# ESP_CO2_V0_30.net
KiCad netlist of a schematic drawn in EAGLE
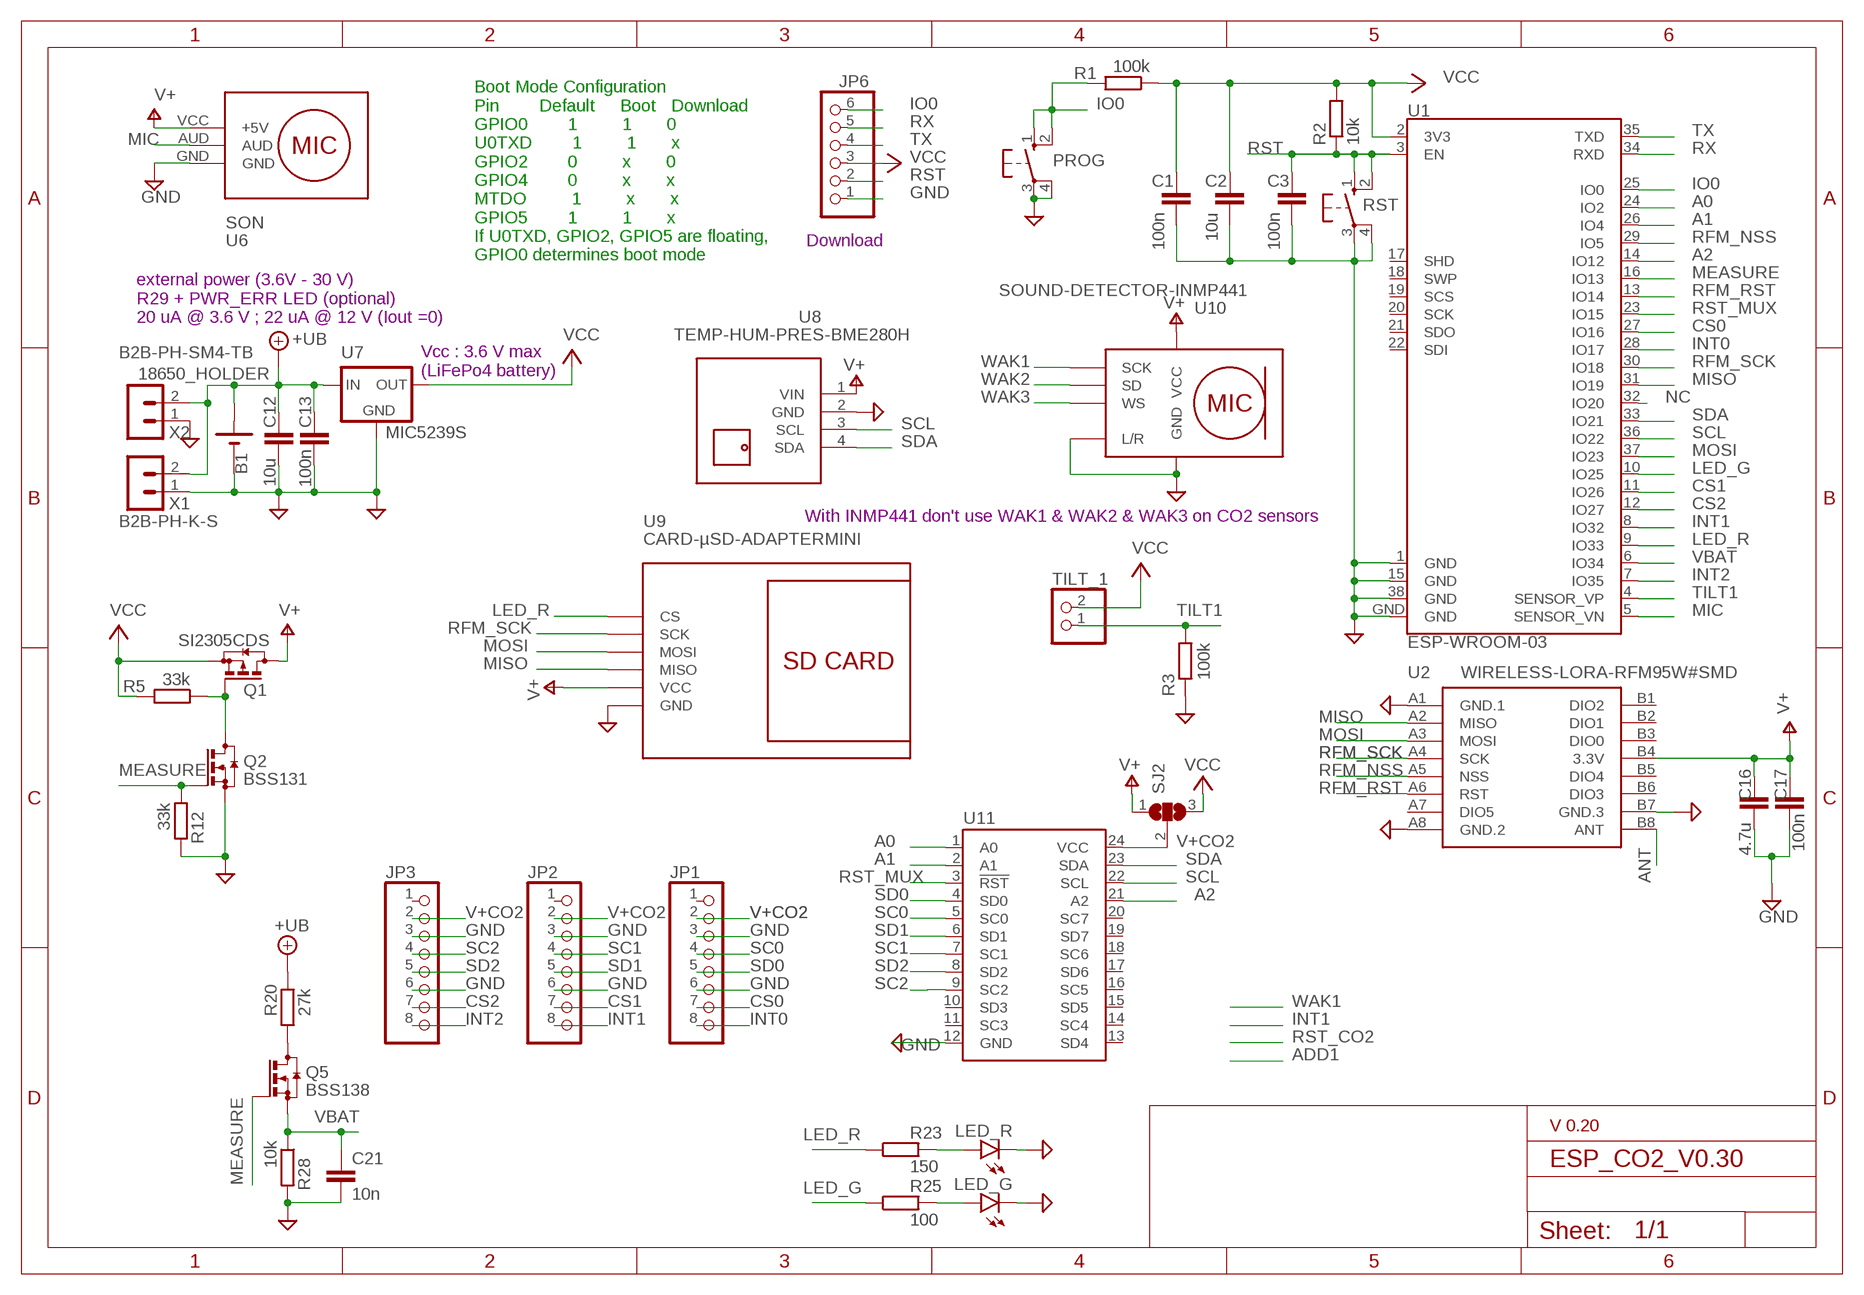
[diagram p0: schematic, sheet 1]

(export (version "E")
  (design (tool "Eeschema 10.0.6"))
  (components
    (comp (ref "B1")
      (value "18650_HOLDER")
      (footprint "eagle-import:18650")
      (libsource (lib "eagle-import") (part "18650_HOLDER"))
    )
    (comp (ref "C1")
      (value "100n")
      (footprint "eagle-import:C1206")
      (libsource (lib "eagle-import") (part "CC1206"))
    )
    (comp (ref "C2")
      (value "10u")
      (footprint "eagle-import:C1206")
      (libsource (lib "eagle-import") (part "CC1206"))
    )
    (comp (ref "C3")
      (value "100n")
      (footprint "eagle-import:C1206")
      (libsource (lib "eagle-import") (part "CC1206"))
    )
    (comp (ref "C12")
      (value "10u")
      (footprint "eagle-import:C1206")
      (libsource (lib "eagle-import") (part "CC1206"))
    )
    (comp (ref "C13")
      (value "100n")
      (footprint "eagle-import:C1206")
      (libsource (lib "eagle-import") (part "CC1206"))
    )
    (comp (ref "C16")
      (value "4.7u")
      (footprint "eagle-import:C1206")
      (libsource (lib "eagle-import") (part "CC1206"))
    )
    (comp (ref "C17")
      (value "100n")
      (footprint "eagle-import:C1206")
      (libsource (lib "eagle-import") (part "CC1206"))
    )
    (comp (ref "C21")
      (value "10n")
      (footprint "eagle-import:C1206")
      (libsource (lib "eagle-import") (part "CC1206"))
    )
    (comp (ref "JP1")
      (value "PINHD-1X8")
      (footprint "eagle-import:1X08")
      (libsource (lib "eagle-import") (part "PINHD-1X8"))
    )
    (comp (ref "JP2")
      (value "PINHD-1X8")
      (footprint "eagle-import:1X08")
      (libsource (lib "eagle-import") (part "PINHD-1X8"))
    )
    (comp (ref "JP3")
      (value "PINHD-1X8")
      (footprint "eagle-import:1X08")
      (libsource (lib "eagle-import") (part "PINHD-1X8"))
    )
    (comp (ref "JP6")
      (value "PINHD-1X6/90")
      (footprint "eagle-import:1X06_90")
      (libsource (lib "eagle-import") (part "PINHD-1X6/90"))
    )
    (comp (ref "LED_G")
      (value "LEDSML0805")
      (footprint "eagle-import:SML0805")
      (libsource (lib "eagle-import") (part "LEDSML0805"))
    )
    (comp (ref "LED_R")
      (value "LEDSML0805")
      (footprint "eagle-import:SML0805")
      (libsource (lib "eagle-import") (part "LEDSML0805"))
    )
    (comp (ref "PROG")
      (value "10-XX")
      (footprint "eagle-import:B3F-10XX")
      (fields (field (name "MPN") "B3F-1000"))
      (libsource (lib "eagle-import") (part "10-XX"))
    )
    (comp (ref "Q1")
      (value "SI2305CDS")
      (footprint "eagle-import:SOT23")
      (libsource (lib "eagle-import") (part "SI2305CDS"))
    )
    (comp (ref "Q2")
      (value "BSS131")
      (footprint "eagle-import:SOT23")
      (libsource (lib "eagle-import") (part "BSS131"))
    )
    (comp (ref "Q5")
      (value "BSS138")
      (footprint "eagle-import:SOT23")
      (libsource (lib "eagle-import") (part "BSS138"))
    )
    (comp (ref "R1")
      (value "100k")
      (footprint "eagle-import:R1206")
      (libsource (lib "eagle-import") (part "RR1206"))
    )
    (comp (ref "R2")
      (value "10k")
      (footprint "eagle-import:R1206")
      (libsource (lib "eagle-import") (part "RR1206"))
    )
    (comp (ref "R3")
      (value "100k")
      (footprint "eagle-import:R1206")
      (libsource (lib "eagle-import") (part "RR1206"))
    )
    (comp (ref "R5")
      (value "33k")
      (footprint "eagle-import:R1206")
      (libsource (lib "eagle-import") (part "RR1206"))
    )
    (comp (ref "R12")
      (value "33k")
      (footprint "eagle-import:R1206")
      (libsource (lib "eagle-import") (part "RR1206"))
    )
    (comp (ref "R20")
      (value "27k")
      (footprint "eagle-import:R1206")
      (libsource (lib "eagle-import") (part "RR1206"))
    )
    (comp (ref "R23")
      (value "150")
      (footprint "eagle-import:R1206")
      (libsource (lib "eagle-import") (part "RR1206"))
    )
    (comp (ref "R25")
      (value "100")
      (footprint "eagle-import:R1206")
      (libsource (lib "eagle-import") (part "RR1206"))
    )
    (comp (ref "R28")
      (value "10k")
      (footprint "eagle-import:R1206")
      (libsource (lib "eagle-import") (part "RR1206"))
    )
    (comp (ref "RST")
      (value "10-XX")
      (footprint "eagle-import:B3F-10XX")
      (fields (field (name "MPN") "B3F-1000"))
      (libsource (lib "eagle-import") (part "10-XX"))
    )
    (comp (ref "SJ2")
      (value "SJ2W")
      (footprint "eagle-import:SJ_2")
      (libsource (lib "eagle-import") (part "SJ2W"))
    )
    (comp (ref "TILT_1")
      (value "PINHD-1X2")
      (footprint "eagle-import:1X02")
      (libsource (lib "eagle-import") (part "PINHD-1X2"))
    )
    (comp (ref "U1")
      (value "ESP-WROOM-03")
      (footprint "eagle-import:ESP-WROOM-03")
      (libsource (lib "eagle-import") (part "ESP-WROOM-03"))
    )
    (comp (ref "U2")
      (value "WIRELESS-LORA-RFM95W#SMD")
      (footprint "eagle-import:WIRELESS-LORA-RFM95W#SMD")
      (libsource (lib "eagle-import") (part "WIRELESS-LORA-RFM95W#SMD"))
    )
    (comp (ref "U6")
      (value "SON")
      (footprint "eagle-import:SON")
      (libsource (lib "eagle-import") (part "SON"))
    )
    (comp (ref "U7")
      (value "MIC5239S")
      (footprint "eagle-import:SOT223")
      (libsource (lib "eagle-import") (part "MIC5239S"))
    )
    (comp (ref "U8")
      (value "TEMP-HUM-PRES-BME280H")
      (footprint "eagle-import:TEMP-HUM-PRES-BME280-H")
      (libsource (lib "eagle-import") (part "TEMP-HUM-PRES-BME280H"))
    )
    (comp (ref "U9")
      (value "CARD-µSD-ADAPTERMINI")
      (footprint "eagle-import:CARD-MINI--µSD-READER")
      (libsource (lib "eagle-import") (part "CARD-µSD-ADAPTERMINI"))
    )
    (comp (ref "U10")
      (value "SOUND-DETECTOR-INMP441")
      (footprint "eagle-import:SOUND-DETECTOR-INMP441")
      (libsource (lib "eagle-import") (part "SOUND-DETECTOR-INMP441"))
    )
    (comp (ref "U11")
      (value "PCA9548A")
      (footprint "eagle-import:TSSOP28")
      (libsource (lib "eagle-import") (part "PCA9548A"))
    )
    (comp (ref "X1")
      (value "B2B-PH-K-S")
      (footprint "eagle-import:B2B-PH-K-S")
      (libsource (lib "eagle-import") (part "B2B-PH-K-S"))
    )
    (comp (ref "X2")
      (value "B2B-PH-SM4-TB")
      (footprint "eagle-import:B2B-PH-SM4-TB")
      (libsource (lib "eagle-import") (part "B2B-PH-SM4-TB"))
    )
  )
  (nets
    (net (code "1") (name "+UB") (class "Default")
      (node (ref "B1") (pin "+") (pinfunction "+_+") (pintype "passive"))
      (node (ref "C12") (pin "1") (pinfunction "1_1") (pintype "passive"))
      (node (ref "C13") (pin "1") (pinfunction "1_1") (pintype "passive"))
      (node (ref "R20") (pin "2") (pinfunction "2_2") (pintype "passive"))
      (node (ref "U7") (pin "1") (pinfunction "IN_1") (pintype "input"))
      (node (ref "X1") (pin "2") (pinfunction "2_2") (pintype "passive"))
      (node (ref "X2") (pin "2") (pinfunction "2_2") (pintype "passive"))
    )
    (net (code "2") (name "/A0") (class "Default")
      (node (ref "U1") (pin "24") (pinfunction "IO2_24") (pintype "bidirectional"))
      (node (ref "U11") (pin "1") (pinfunction "A0_1") (pintype "bidirectional"))
    )
    (net (code "3") (name "/A1") (class "Default")
      (node (ref "U1") (pin "26") (pinfunction "IO4_26") (pintype "bidirectional"))
      (node (ref "U11") (pin "2") (pinfunction "A1_2") (pintype "bidirectional"))
    )
    (net (code "4") (name "/A2") (class "Default")
      (node (ref "U1") (pin "14") (pinfunction "IO12_14") (pintype "bidirectional"))
      (node (ref "U11") (pin "21") (pinfunction "A2_21") (pintype "bidirectional"))
    )
    (net (code "6") (name "/ANT") (class "Default")
      (node (ref "U2") (pin "B8") (pinfunction "ANT_B8") (pintype "passive"))
    )
    (net (code "7") (name "/CS0") (class "Default")
      (node (ref "JP1") (pin "7") (pinfunction "7_7") (pintype "passive"))
      (node (ref "U1") (pin "27") (pinfunction "IO16_27") (pintype "bidirectional"))
    )
    (net (code "8") (name "/CS1") (class "Default")
      (node (ref "JP2") (pin "7") (pinfunction "7_7") (pintype "passive"))
      (node (ref "U1") (pin "11") (pinfunction "IO26_11") (pintype "bidirectional"))
    )
    (net (code "9") (name "/CS2") (class "Default")
      (node (ref "JP3") (pin "7") (pinfunction "7_7") (pintype "passive"))
      (node (ref "U1") (pin "12") (pinfunction "IO27_12") (pintype "bidirectional"))
    )
    (net (code "10") (name "/INT0") (class "Default")
      (node (ref "JP1") (pin "8") (pinfunction "8_8") (pintype "passive"))
      (node (ref "U1") (pin "28") (pinfunction "IO17_28") (pintype "bidirectional"))
    )
    (net (code "11") (name "/INT1") (class "Default")
      (node (ref "JP2") (pin "8") (pinfunction "8_8") (pintype "passive"))
      (node (ref "U1") (pin "8") (pinfunction "IO32_8") (pintype "bidirectional"))
    )
    (net (code "12") (name "/INT2") (class "Default")
      (node (ref "JP3") (pin "8") (pinfunction "8_8") (pintype "passive"))
      (node (ref "U1") (pin "7") (pinfunction "IO35_7") (pintype "bidirectional"))
    )
    (net (code "13") (name "/IO0") (class "Default")
      (node (ref "JP6") (pin "6") (pinfunction "6_6") (pintype "passive"))
      (node (ref "PROG") (pin "1") (pinfunction "S_1") (pintype "passive"))
      (node (ref "PROG") (pin "2") (pinfunction "S1_2") (pintype "passive"))
      (node (ref "R1") (pin "2") (pinfunction "2_2") (pintype "passive"))
      (node (ref "U1") (pin "25") (pinfunction "IO0_25") (pintype "bidirectional"))
    )
    (net (code "14") (name "/LED_G") (class "Default")
      (node (ref "R25") (pin "1") (pinfunction "1_1") (pintype "passive"))
      (node (ref "U1") (pin "10") (pinfunction "IO25_10") (pintype "bidirectional"))
    )
    (net (code "15") (name "/LED_R") (class "Default")
      (node (ref "R23") (pin "1") (pinfunction "1_1") (pintype "passive"))
      (node (ref "U1") (pin "9") (pinfunction "IO33_9") (pintype "bidirectional"))
      (node (ref "U9") (pin "CS") (pinfunction "CS_CS") (pintype "bidirectional"))
    )
    (net (code "16") (name "/MEASURE") (class "Default")
      (node (ref "Q2") (pin "1") (pinfunction "G_1") (pintype "passive"))
      (node (ref "Q5") (pin "1") (pinfunction "G_1") (pintype "passive"))
      (node (ref "R12") (pin "1") (pinfunction "1_1") (pintype "passive"))
      (node (ref "U1") (pin "16") (pinfunction "IO13_16") (pintype "bidirectional"))
    )
    (net (code "17") (name "/MIC") (class "Default")
      (node (ref "U1") (pin "5") (pinfunction "SENSOR_VN_5") (pintype "bidirectional"))
      (node (ref "U6") (pin "AUD") (pinfunction "AUD_AUD") (pintype "output"))
    )
    (net (code "18") (name "/MISO") (class "Default")
      (node (ref "U1") (pin "31") (pinfunction "IO19_31") (pintype "bidirectional"))
      (node (ref "U2") (pin "A2") (pinfunction "MISO_A2") (pintype "bidirectional"))
      (node (ref "U9") (pin "MISO") (pinfunction "MISO_MISO") (pintype "bidirectional"))
    )
    (net (code "19") (name "/MOSI") (class "Default")
      (node (ref "U1") (pin "37") (pinfunction "IO23_37") (pintype "bidirectional"))
      (node (ref "U2") (pin "A3") (pinfunction "MOSI_A3") (pintype "bidirectional"))
      (node (ref "U9") (pin "MOSI") (pinfunction "MOSI_MOSI") (pintype "bidirectional"))
    )
    (net (code "20") (name "/NC") (class "Default")
      (node (ref "U1") (pin "32") (pinfunction "IO20_32") (pintype "bidirectional"))
    )
    (net (code "21") (name "/RFM_NSS") (class "Default")
      (node (ref "U1") (pin "29") (pinfunction "IO5_29") (pintype "bidirectional"))
      (node (ref "U2") (pin "A5") (pinfunction "NSS_A5") (pintype "bidirectional"))
    )
    (net (code "22") (name "/RFM_RST") (class "Default")
      (node (ref "U1") (pin "13") (pinfunction "IO14_13") (pintype "bidirectional"))
      (node (ref "U2") (pin "A6") (pinfunction "RST_A6") (pintype "bidirectional"))
    )
    (net (code "23") (name "/RFM_SCK") (class "Default")
      (node (ref "U1") (pin "30") (pinfunction "IO18_30") (pintype "bidirectional"))
      (node (ref "U2") (pin "A4") (pinfunction "SCK_A4") (pintype "bidirectional"))
      (node (ref "U9") (pin "SCK") (pinfunction "SCK_SCK") (pintype "bidirectional"))
    )
    (net (code "24") (name "/RST") (class "Default")
      (node (ref "C3") (pin "1") (pinfunction "1_1") (pintype "passive"))
      (node (ref "JP6") (pin "2") (pinfunction "2_2") (pintype "passive"))
      (node (ref "R2") (pin "1") (pinfunction "1_1") (pintype "passive"))
      (node (ref "RST") (pin "1") (pinfunction "S_1") (pintype "passive"))
      (node (ref "RST") (pin "2") (pinfunction "S1_2") (pintype "passive"))
      (node (ref "U1") (pin "3") (pinfunction "EN_3") (pintype "bidirectional"))
    )
    (net (code "26") (name "/RST_MUX") (class "Default")
      (node (ref "U1") (pin "23") (pinfunction "IO15_23") (pintype "bidirectional"))
      (node (ref "U11") (pin "3") (pinfunction "~{RST}_3") (pintype "bidirectional"))
    )
    (net (code "27") (name "/RX") (class "Default")
      (node (ref "JP6") (pin "5") (pinfunction "5_5") (pintype "passive"))
      (node (ref "U1") (pin "34") (pinfunction "RXD_34") (pintype "bidirectional"))
    )
    (net (code "28") (name "/SC0") (class "Default")
      (node (ref "JP1") (pin "4") (pinfunction "4_4") (pintype "passive"))
      (node (ref "U11") (pin "5") (pinfunction "SC0_5") (pintype "bidirectional"))
    )
    (net (code "29") (name "/SC1") (class "Default")
      (node (ref "JP2") (pin "4") (pinfunction "4_4") (pintype "passive"))
      (node (ref "U11") (pin "7") (pinfunction "SC1_7") (pintype "bidirectional"))
    )
    (net (code "30") (name "/SC2") (class "Default")
      (node (ref "JP3") (pin "4") (pinfunction "4_4") (pintype "passive"))
      (node (ref "U11") (pin "9") (pinfunction "SC2_9") (pintype "bidirectional"))
    )
    (net (code "31") (name "/SCL") (class "Default")
      (node (ref "U1") (pin "36") (pinfunction "IO22_36") (pintype "bidirectional"))
      (node (ref "U11") (pin "22") (pinfunction "SCL_22") (pintype "bidirectional"))
      (node (ref "U8") (pin "3") (pinfunction "SCL_3") (pintype "bidirectional"))
    )
    (net (code "32") (name "/SD0") (class "Default")
      (node (ref "JP1") (pin "5") (pinfunction "5_5") (pintype "passive"))
      (node (ref "U11") (pin "4") (pinfunction "SD0_4") (pintype "bidirectional"))
    )
    (net (code "33") (name "/SD1") (class "Default")
      (node (ref "JP2") (pin "5") (pinfunction "5_5") (pintype "passive"))
      (node (ref "U11") (pin "6") (pinfunction "SD1_6") (pintype "bidirectional"))
    )
    (net (code "34") (name "/SD2") (class "Default")
      (node (ref "JP3") (pin "5") (pinfunction "5_5") (pintype "passive"))
      (node (ref "U11") (pin "8") (pinfunction "SD2_8") (pintype "bidirectional"))
    )
    (net (code "35") (name "/SDA") (class "Default")
      (node (ref "U1") (pin "33") (pinfunction "IO21_33") (pintype "bidirectional"))
      (node (ref "U11") (pin "23") (pinfunction "SDA_23") (pintype "bidirectional"))
      (node (ref "U8") (pin "4") (pinfunction "SDA_4") (pintype "bidirectional"))
    )
    (net (code "36") (name "/TILT1") (class "Default")
      (node (ref "R3") (pin "1") (pinfunction "1_1") (pintype "passive"))
      (node (ref "TILT_1") (pin "1") (pinfunction "1_1") (pintype "passive"))
      (node (ref "U1") (pin "4") (pinfunction "SENSOR_VP_4") (pintype "bidirectional"))
    )
    (net (code "37") (name "/TX") (class "Default")
      (node (ref "JP6") (pin "4") (pinfunction "4_4") (pintype "passive"))
      (node (ref "U1") (pin "35") (pinfunction "TXD_35") (pintype "bidirectional"))
    )
    (net (code "38") (name "/V+CO2") (class "Default")
      (node (ref "JP1") (pin "2") (pinfunction "2_2") (pintype "passive"))
      (node (ref "JP2") (pin "2") (pinfunction "2_2") (pintype "passive"))
      (node (ref "JP3") (pin "2") (pinfunction "2_2") (pintype "passive"))
      (node (ref "SJ2") (pin "2") (pinfunction "2_2") (pintype "passive"))
      (node (ref "U11") (pin "24") (pinfunction "VCC_24") (pintype "bidirectional"))
    )
    (net (code "39") (name "/VBAT") (class "Default")
      (node (ref "C21") (pin "1") (pinfunction "1_1") (pintype "passive"))
      (node (ref "Q5") (pin "2") (pinfunction "S_2") (pintype "passive"))
      (node (ref "R28") (pin "1") (pinfunction "1_1") (pintype "passive"))
      (node (ref "U1") (pin "6") (pinfunction "IO34_6") (pintype "bidirectional"))
    )
    (net (code "40") (name "/WAK1") (class "Default")
      (node (ref "U10") (pin "SCK") (pinfunction "SCK_SCK") (pintype "output"))
    )
    (net (code "41") (name "/WAK2") (class "Default")
      (node (ref "U10") (pin "SD") (pinfunction "SD_SD") (pintype "output"))
    )
    (net (code "42") (name "/WAK3") (class "Default")
      (node (ref "U10") (pin "WS") (pinfunction "WS_WS") (pintype "output"))
    )
    (net (code "43") (name "GND") (class "Default")
      (node (ref "B1") (pin "-") (pinfunction "-_-") (pintype "passive"))
      (node (ref "C1") (pin "2") (pinfunction "2_2") (pintype "passive"))
      (node (ref "C12") (pin "2") (pinfunction "2_2") (pintype "passive"))
      (node (ref "C13") (pin "2") (pinfunction "2_2") (pintype "passive"))
      (node (ref "C16") (pin "2") (pinfunction "2_2") (pintype "passive"))
      (node (ref "C17") (pin "2") (pinfunction "2_2") (pintype "passive"))
      (node (ref "C2") (pin "2") (pinfunction "2_2") (pintype "passive"))
      (node (ref "C21") (pin "2") (pinfunction "2_2") (pintype "passive"))
      (node (ref "C3") (pin "2") (pinfunction "2_2") (pintype "passive"))
      (node (ref "JP1") (pin "3") (pinfunction "3_3") (pintype "passive"))
      (node (ref "JP1") (pin "6") (pinfunction "6_6") (pintype "passive"))
      (node (ref "JP2") (pin "3") (pinfunction "3_3") (pintype "passive"))
      (node (ref "JP2") (pin "6") (pinfunction "6_6") (pintype "passive"))
      (node (ref "JP3") (pin "3") (pinfunction "3_3") (pintype "passive"))
      (node (ref "JP3") (pin "6") (pinfunction "6_6") (pintype "passive"))
      (node (ref "JP6") (pin "1") (pinfunction "1_1") (pintype "passive"))
      (node (ref "LED_G") (pin "C") (pinfunction "C_C") (pintype "passive"))
      (node (ref "LED_R") (pin "C") (pinfunction "C_C") (pintype "passive"))
      (node (ref "PROG") (pin "3") (pinfunction "P_3") (pintype "passive"))
      (node (ref "PROG") (pin "4") (pinfunction "P1_4") (pintype "passive"))
      (node (ref "Q2") (pin "2") (pinfunction "S_2") (pintype "passive"))
      (node (ref "R12") (pin "2") (pinfunction "2_2") (pintype "passive"))
      (node (ref "R28") (pin "2") (pinfunction "2_2") (pintype "passive"))
      (node (ref "R3") (pin "2") (pinfunction "2_2") (pintype "passive"))
      (node (ref "RST") (pin "3") (pinfunction "P_3") (pintype "passive"))
      (node (ref "RST") (pin "4") (pinfunction "P1_4") (pintype "passive"))
      (node (ref "U1") (pin "1") (pinfunction "GND_1") (pintype "bidirectional"))
      (node (ref "U1") (pin "15") (pinfunction "GND_15") (pintype "bidirectional"))
      (node (ref "U1") (pin "38") (pinfunction "GND_38") (pintype "bidirectional"))
      (node (ref "U1") (pin "GND") (pinfunction "GND_GND") (pintype "bidirectional"))
      (node (ref "U10") (pin "GND") (pinfunction "GND_GND") (pintype "power_in"))
      (node (ref "U10") (pin "L/R") (pinfunction "L/R_L/R") (pintype "output"))
      (node (ref "U11") (pin "12") (pinfunction "GND_12") (pintype "bidirectional"))
      (node (ref "U2") (pin "A1") (pinfunction "GND.1_A1") (pintype "power_in"))
      (node (ref "U2") (pin "A8") (pinfunction "GND.2_A8") (pintype "power_in"))
      (node (ref "U2") (pin "B7") (pinfunction "GND.3_B7") (pintype "power_in"))
      (node (ref "U6") (pin "GND") (pinfunction "GND_GND") (pintype "power_in"))
      (node (ref "U7") (pin "2") (pinfunction "GND_2") (pintype "passive"))
      (node (ref "U7") (pin "4") (pinfunction "GND_4") (pintype "passive"))
      (node (ref "U8") (pin "2") (pinfunction "GND_2") (pintype "power_in"))
      (node (ref "U9") (pin "GND") (pinfunction "GND_GND") (pintype "power_in"))
      (node (ref "X1") (pin "1") (pinfunction "1_1") (pintype "passive"))
      (node (ref "X2") (pin "1") (pinfunction "1_1") (pintype "passive"))
    )
    (net (code "44") (name "Net-(LED_G-PadA)") (class "Default")
      (node (ref "LED_G") (pin "A") (pinfunction "A_A") (pintype "passive"))
      (node (ref "R25") (pin "2") (pinfunction "2_2") (pintype "passive"))
    )
    (net (code "45") (name "Net-(LED_R-PadA)") (class "Default")
      (node (ref "LED_R") (pin "A") (pinfunction "A_A") (pintype "passive"))
      (node (ref "R23") (pin "2") (pinfunction "2_2") (pintype "passive"))
    )
    (net (code "46") (name "Net-(Q1-G)") (class "Default")
      (node (ref "Q1") (pin "1") (pinfunction "G_1") (pintype "passive"))
      (node (ref "Q2") (pin "3") (pinfunction "D_3") (pintype "passive"))
      (node (ref "R5") (pin "1") (pinfunction "1_1") (pintype "passive"))
    )
    (net (code "47") (name "Net-(Q5-D)") (class "Default")
      (node (ref "Q5") (pin "3") (pinfunction "D_3") (pintype "passive"))
      (node (ref "R20") (pin "1") (pinfunction "1_1") (pintype "passive"))
    )
    (net (code "48") (name "V+") (class "Default")
      (node (ref "C16") (pin "1") (pinfunction "1_1") (pintype "passive"))
      (node (ref "C17") (pin "1") (pinfunction "1_1") (pintype "passive"))
      (node (ref "Q1") (pin "3") (pinfunction "D_3") (pintype "passive"))
      (node (ref "SJ2") (pin "1") (pinfunction "1_1") (pintype "passive"))
      (node (ref "U10") (pin "VDD") (pinfunction "VCC_VDD") (pintype "power_in"))
      (node (ref "U2") (pin "B4") (pinfunction "3.3V_B4") (pintype "power_in"))
      (node (ref "U6") (pin "VCC") (pinfunction "+5V_VCC") (pintype "power_in"))
      (node (ref "U8") (pin "1") (pinfunction "VIN_1") (pintype "power_in"))
      (node (ref "U9") (pin "VCC") (pinfunction "VCC_VCC") (pintype "power_in"))
    )
    (net (code "49") (name "VCC") (class "Default")
      (node (ref "C1") (pin "1") (pinfunction "1_1") (pintype "passive"))
      (node (ref "C2") (pin "1") (pinfunction "1_1") (pintype "passive"))
      (node (ref "JP6") (pin "3") (pinfunction "3_3") (pintype "passive"))
      (node (ref "Q1") (pin "2") (pinfunction "S_2") (pintype "passive"))
      (node (ref "R1") (pin "1") (pinfunction "1_1") (pintype "passive"))
      (node (ref "R2") (pin "2") (pinfunction "2_2") (pintype "passive"))
      (node (ref "R5") (pin "2") (pinfunction "2_2") (pintype "passive"))
      (node (ref "SJ2") (pin "3") (pinfunction "3_3") (pintype "passive"))
      (node (ref "TILT_1") (pin "2") (pinfunction "2_2") (pintype "passive"))
      (node (ref "U1") (pin "2") (pinfunction "3V3_2") (pintype "bidirectional"))
      (node (ref "U7") (pin "3") (pinfunction "OUT_3") (pintype "passive"))
    )
    (net (code "50") (name "unconnected-(JP1-Pad1)") (class "Default")
      (node (ref "JP1") (pin "1") (pinfunction "1_1") (pintype "passive"))
    )
    (net (code "51") (name "unconnected-(JP2-Pad1)") (class "Default")
      (node (ref "JP2") (pin "1") (pinfunction "1_1") (pintype "passive"))
    )
    (net (code "52") (name "unconnected-(JP3-Pad1)") (class "Default")
      (node (ref "JP3") (pin "1") (pinfunction "1_1") (pintype "passive"))
    )
    (net (code "53") (name "unconnected-(U1-SCK-Pad20)") (class "Default")
      (node (ref "U1") (pin "20") (pinfunction "SCK_20") (pintype "bidirectional"))
    )
    (net (code "54") (name "unconnected-(U1-SCS-Pad19)") (class "Default")
      (node (ref "U1") (pin "19") (pinfunction "SCS_19") (pintype "bidirectional"))
    )
    (net (code "55") (name "unconnected-(U1-SDI-Pad22)") (class "Default")
      (node (ref "U1") (pin "22") (pinfunction "SDI_22") (pintype "bidirectional"))
    )
    (net (code "56") (name "unconnected-(U1-SDO-Pad21)") (class "Default")
      (node (ref "U1") (pin "21") (pinfunction "SDO_21") (pintype "bidirectional"))
    )
    (net (code "57") (name "unconnected-(U1-SHD-Pad17)") (class "Default")
      (node (ref "U1") (pin "17") (pinfunction "SHD_17") (pintype "bidirectional"))
    )
    (net (code "58") (name "unconnected-(U1-SWP-Pad18)") (class "Default")
      (node (ref "U1") (pin "18") (pinfunction "SWP_18") (pintype "bidirectional"))
    )
    (net (code "59") (name "unconnected-(U2-DIO0-PadB3)") (class "Default")
      (node (ref "U2") (pin "B3") (pinfunction "DIO0_B3") (pintype "bidirectional"))
    )
    (net (code "60") (name "unconnected-(U2-DIO1-PadB2)") (class "Default")
      (node (ref "U2") (pin "B2") (pinfunction "DIO1_B2") (pintype "bidirectional"))
    )
    (net (code "61") (name "unconnected-(U2-DIO2-PadB1)") (class "Default")
      (node (ref "U2") (pin "B1") (pinfunction "DIO2_B1") (pintype "bidirectional"))
    )
    (net (code "62") (name "unconnected-(U2-DIO3-PadB6)") (class "Default")
      (node (ref "U2") (pin "B6") (pinfunction "DIO3_B6") (pintype "bidirectional"))
    )
    (net (code "63") (name "unconnected-(U2-DIO4-PadB5)") (class "Default")
      (node (ref "U2") (pin "B5") (pinfunction "DIO4_B5") (pintype "bidirectional"))
    )
    (net (code "64") (name "unconnected-(U2-DIO5-PadA7)") (class "Default")
      (node (ref "U2") (pin "A7") (pinfunction "DIO5_A7") (pintype "bidirectional"))
    )
    (net (code "65") (name "unconnected-(U11-SC3-Pad11)") (class "Default")
      (node (ref "U11") (pin "11") (pinfunction "SC3_11") (pintype "bidirectional"))
    )
    (net (code "66") (name "unconnected-(U11-SC4-Pad14)") (class "Default")
      (node (ref "U11") (pin "14") (pinfunction "SC4_14") (pintype "bidirectional"))
    )
    (net (code "67") (name "unconnected-(U11-SC5-Pad16)") (class "Default")
      (node (ref "U11") (pin "16") (pinfunction "SC5_16") (pintype "bidirectional"))
    )
    (net (code "68") (name "unconnected-(U11-SC6-Pad18)") (class "Default")
      (node (ref "U11") (pin "18") (pinfunction "SC6_18") (pintype "bidirectional"))
    )
    (net (code "69") (name "unconnected-(U11-SC7-Pad20)") (class "Default")
      (node (ref "U11") (pin "20") (pinfunction "SC7_20") (pintype "bidirectional"))
    )
    (net (code "70") (name "unconnected-(U11-SD3-Pad10)") (class "Default")
      (node (ref "U11") (pin "10") (pinfunction "SD3_10") (pintype "bidirectional"))
    )
    (net (code "71") (name "unconnected-(U11-SD4-Pad13)") (class "Default")
      (node (ref "U11") (pin "13") (pinfunction "SD4_13") (pintype "bidirectional"))
    )
    (net (code "72") (name "unconnected-(U11-SD5-Pad15)") (class "Default")
      (node (ref "U11") (pin "15") (pinfunction "SD5_15") (pintype "bidirectional"))
    )
    (net (code "73") (name "unconnected-(U11-SD6-Pad17)") (class "Default")
      (node (ref "U11") (pin "17") (pinfunction "SD6_17") (pintype "bidirectional"))
    )
    (net (code "74") (name "unconnected-(U11-SD7-Pad19)") (class "Default")
      (node (ref "U11") (pin "19") (pinfunction "SD7_19") (pintype "bidirectional"))
    )
  )
)
